# tweeq-Proto_BLE.net
KiCad netlist of a schematic drawn in EAGLE
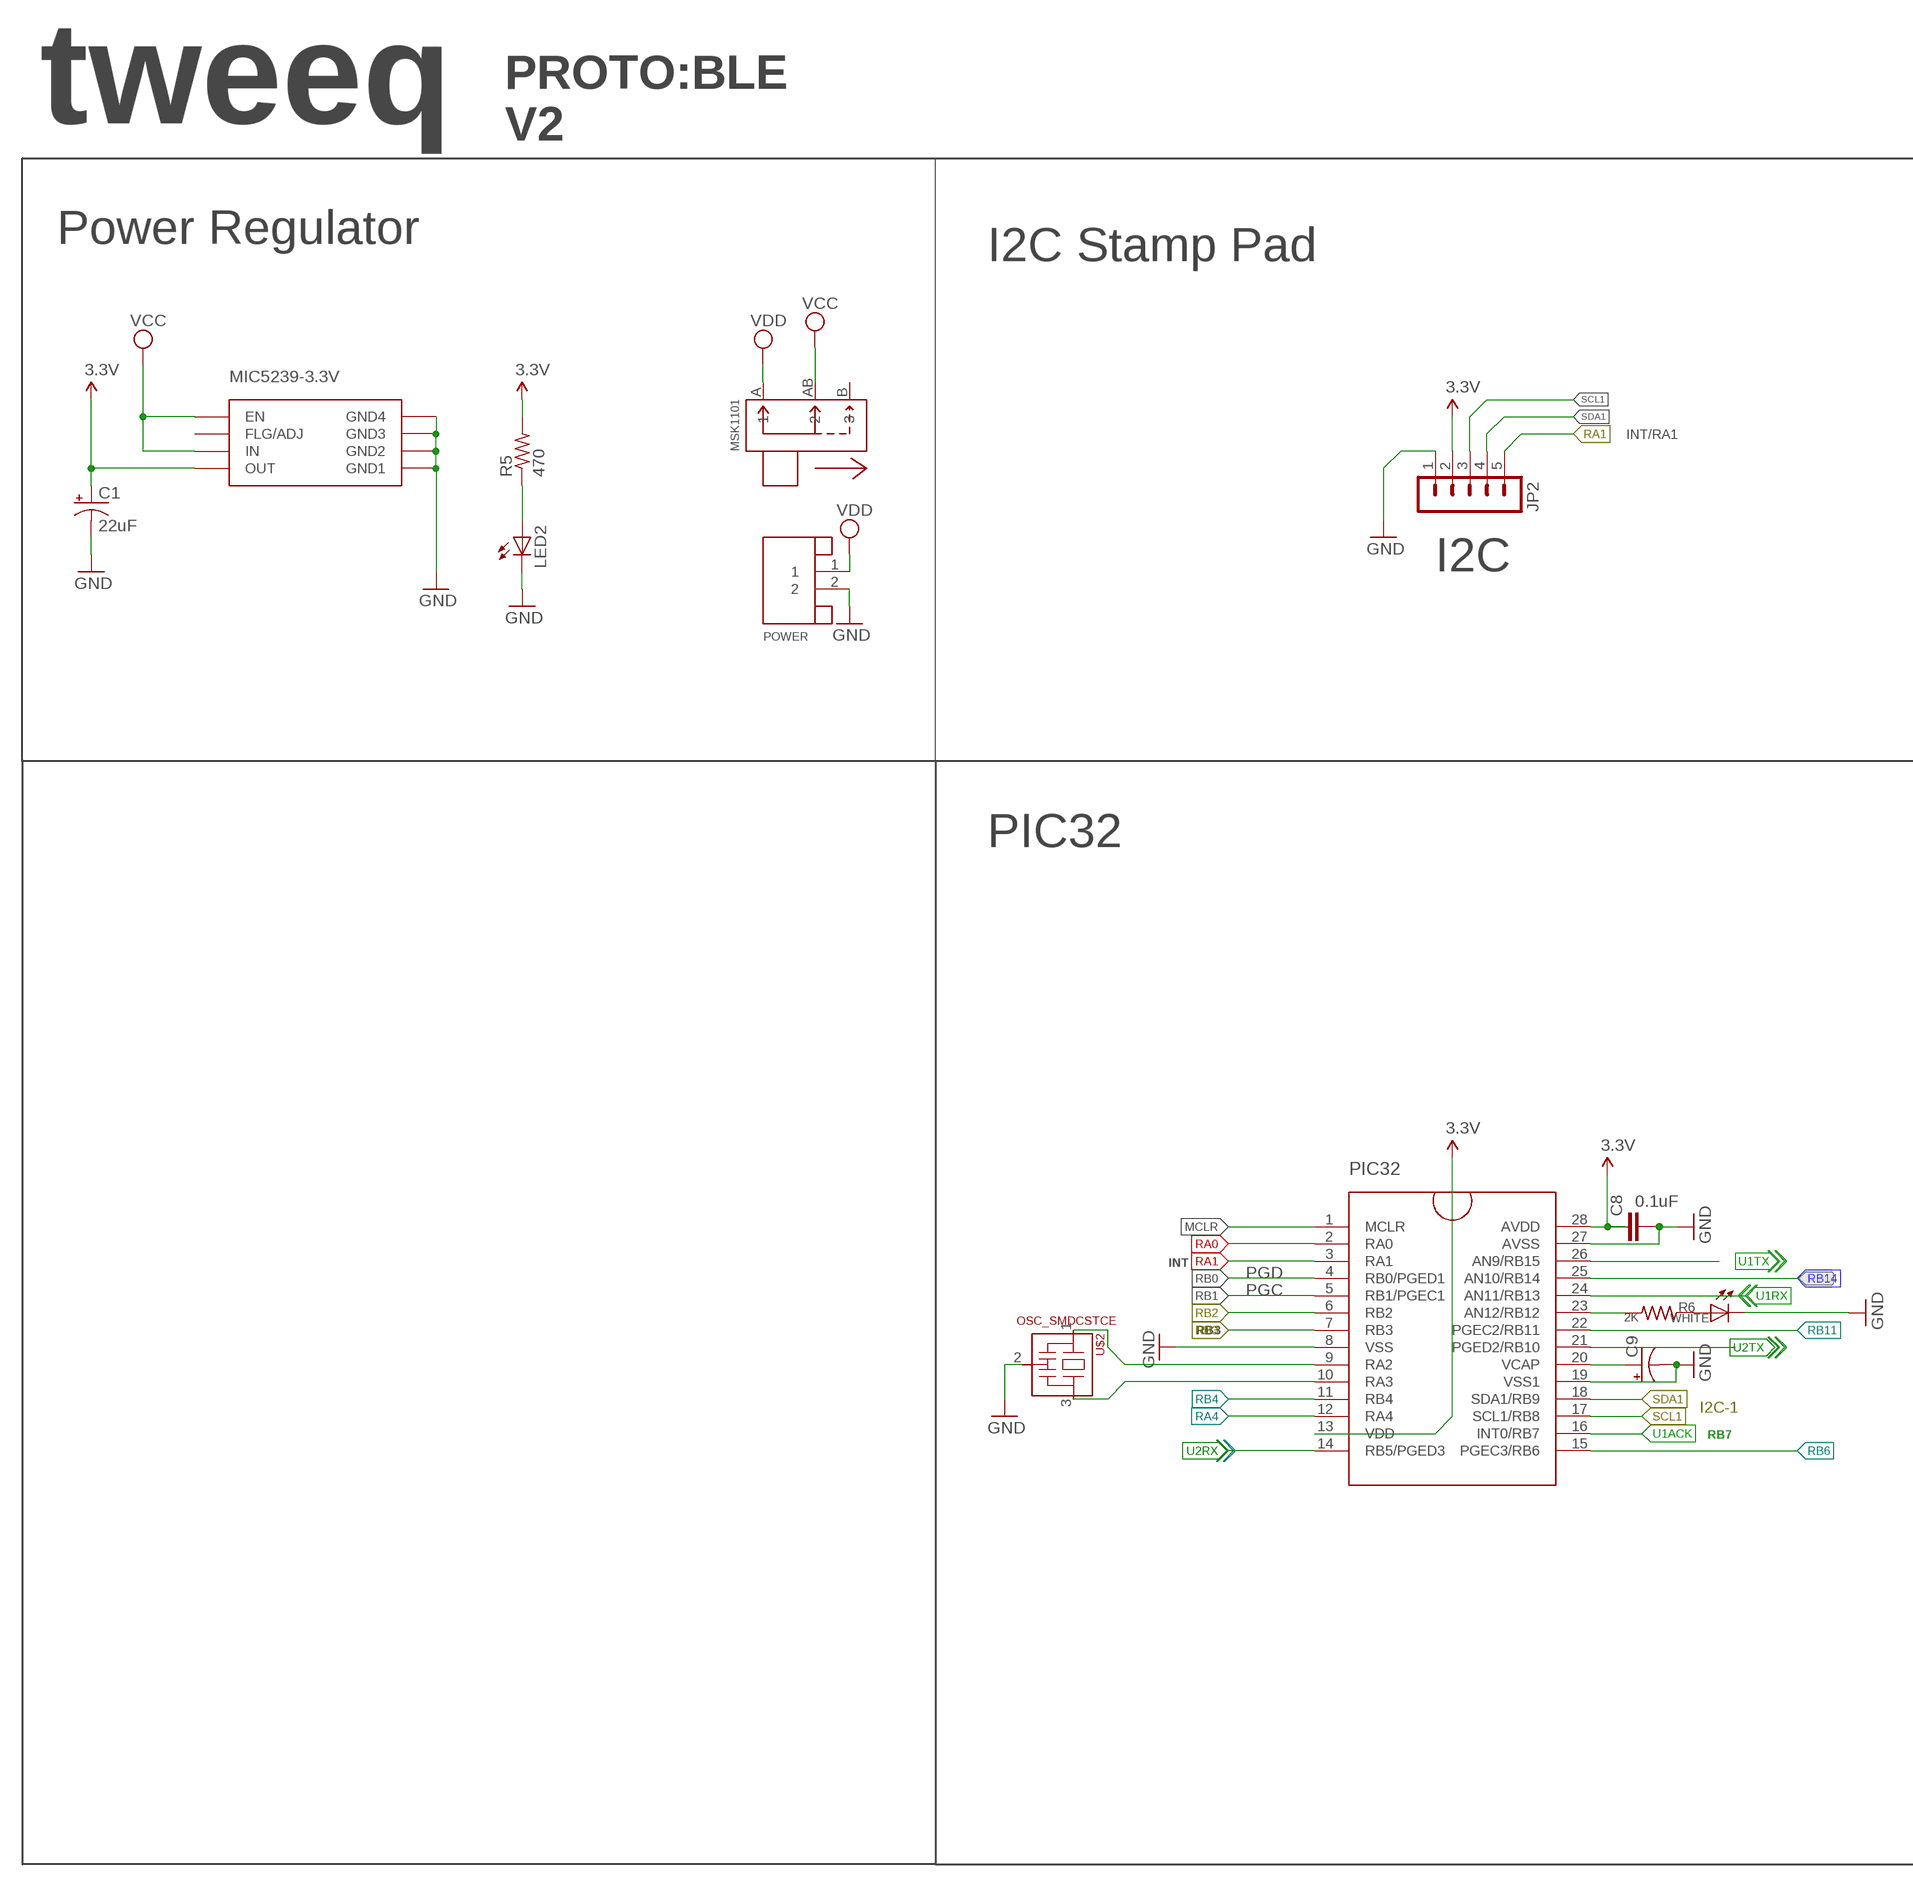
[diagram p0: schematic, sheet 1, part 1 of 2]
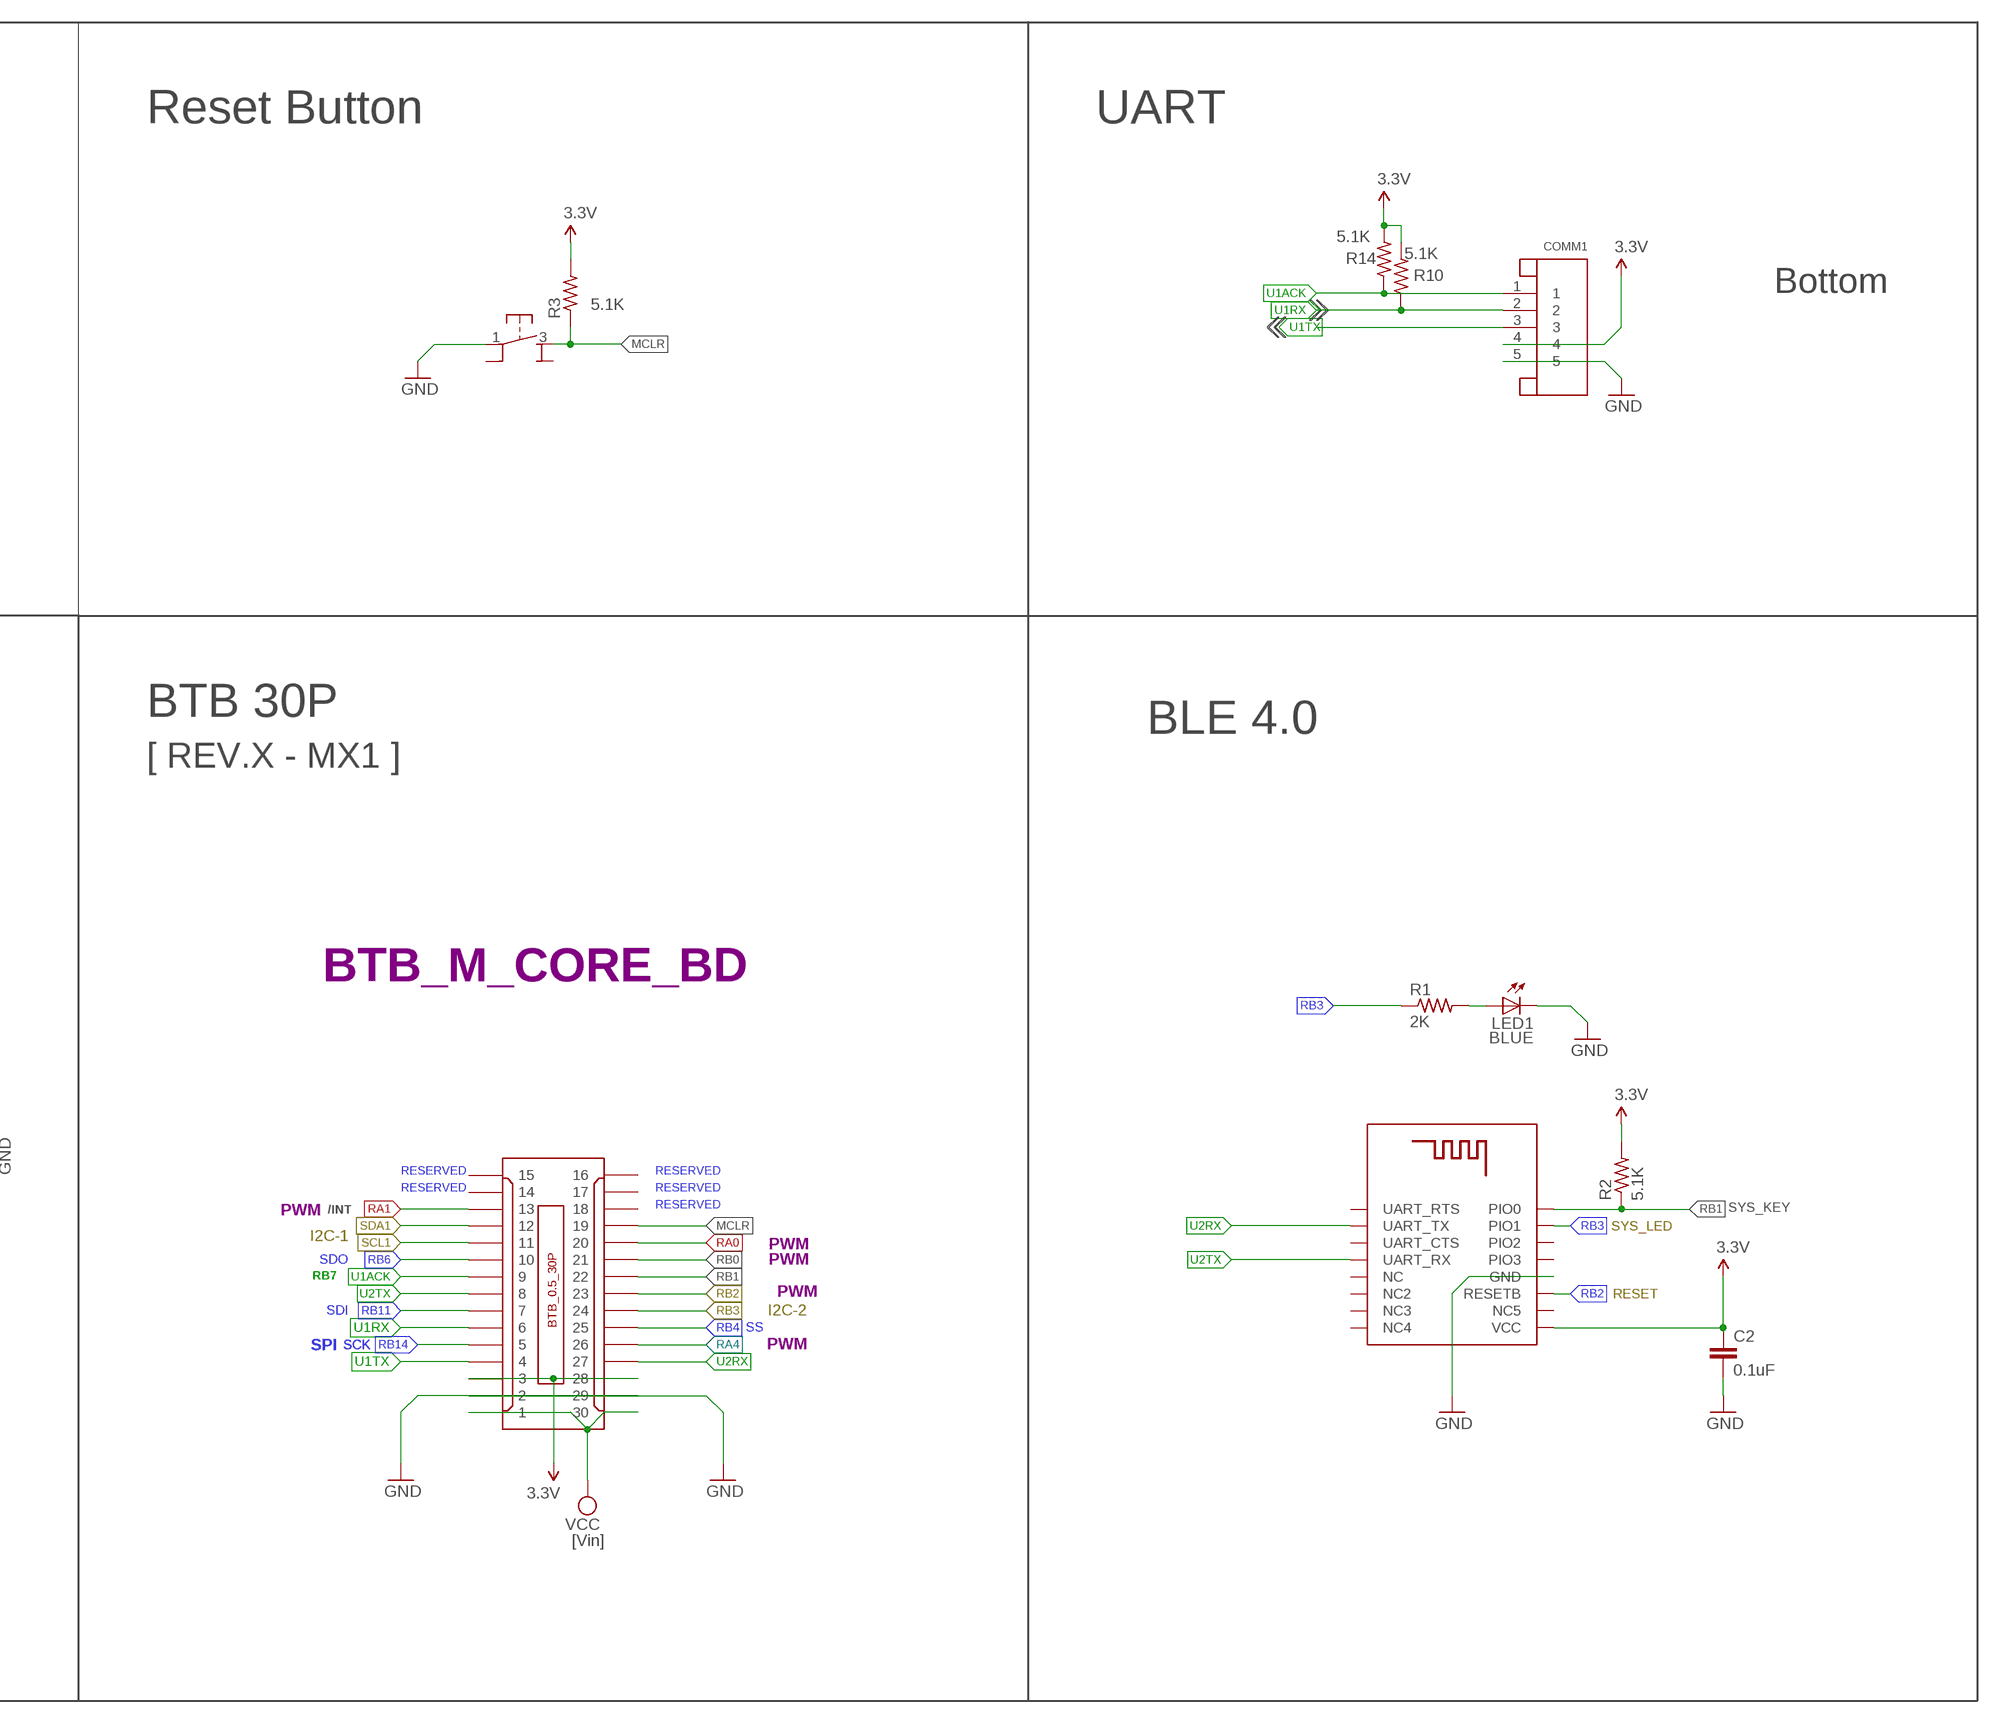
[diagram p1: schematic, sheet 1, part 2 of 2]

(export (version "E")
  (design (tool "Eeschema 10.0.6"))
  (components
    (comp (ref "C1")
      (value "22uF")
      (footprint "eagle-import:SMC_B")
      (libsource (lib "eagle-import") (part "CPOL-USSMCB"))
    )
    (comp (ref "C2")
      (value "0.1uF")
      (footprint "eagle-import:C0402K")
      (libsource (lib "eagle-import") (part "C-EUC0402K"))
    )
    (comp (ref "C8")
      (value "0.1uF")
      (footprint "eagle-import:C0402K")
      (libsource (lib "eagle-import") (part "rcl_C-EUC0402K"))
    )
    (comp (ref "C9")
      (value "CPOL-USA/3216-18R")
      (footprint "eagle-import:A_3216-18R")
      (libsource (lib "eagle-import") (part "CPOL-USA/3216-18R"))
    )
    (comp (ref "COMM1")
      (value "JST-5PINSH")
      (footprint "eagle-import:SH1.0-5PIN")
      (libsource (lib "eagle-import") (part "JST-5PINSH"))
    )
    (comp (ref "JP2")
      (value "M05-11.5MM-SMT")
      (footprint "eagle-import:1X05-1.5MM-SMT")
      (libsource (lib "eagle-import") (part "M05-11.5MM-SMT"))
    )
    (comp (ref "LED1")
      (value "BLUE")
      (footprint "eagle-import:CHIP-LED0805")
      (libsource (lib "eagle-import") (part "LEDCHIP-LED0805"))
    )
    (comp (ref "LED2")
      (value "LEDCHIP-LED0805")
      (footprint "eagle-import:CHIP-LED0805")
      (libsource (lib "eagle-import") (part "LEDCHIP-LED0805"))
    )
    (comp (ref "MIC5239-3.3V")
      (value "MIC5239-MM")
      (footprint "eagle-import:MSOP8")
      (libsource (lib "eagle-import") (part "MIC5239-MM"))
    )
    (comp (ref "MSK1101")
      (value "SLIDE_SWITCH_MINI/MSK1101")
      (footprint "eagle-import:MSK1101")
      (libsource (lib "eagle-import") (part "SLIDE_SWITCH_MINI/MSK1101"))
    )
    (comp (ref "PIC32")
      (value "PIC32MX_1XX_2XX")
      (footprint "eagle-import:SSOP28")
      (libsource (lib "eagle-import") (part "PIC32MX_1XX_2XX"))
    )
    (comp (ref "PIC_LED")
      (value "WHITE")
      (footprint "eagle-import:CHIP-LED0805")
      (libsource (lib "eagle-import") (part "LEDCHIP-LED0805"))
    )
    (comp (ref "POWER")
      (value "JST-2PINSH")
      (footprint "eagle-import:SH1.0-2PIN")
      (libsource (lib "eagle-import") (part "JST-2PINSH"))
    )
    (comp (ref "R1")
      (value "2K")
      (footprint "eagle-import:R0402")
      (libsource (lib "eagle-import") (part "R-US_R0402"))
    )
    (comp (ref "R2")
      (value "5.1K")
      (footprint "eagle-import:R0402")
      (libsource (lib "eagle-import") (part "R-US_R0402"))
    )
    (comp (ref "R3")
      (value "5.1K")
      (footprint "eagle-import:R0402")
      (libsource (lib "eagle-import") (part "R-US_R0402"))
    )
    (comp (ref "R5")
      (value "470")
      (footprint "eagle-import:R0402")
      (libsource (lib "eagle-import") (part "R-US_R0402"))
    )
    (comp (ref "R6")
      (value "2K")
      (footprint "eagle-import:R0402")
      (libsource (lib "eagle-import") (part "R-US_R0402"))
    )
    (comp (ref "R10")
      (value "5.1K")
      (footprint "eagle-import:R0402")
      (libsource (lib "eagle-import") (part "R-US_R0402"))
    )
    (comp (ref "R14")
      (value "5.1K")
      (footprint "eagle-import:R0402")
      (libsource (lib "eagle-import") (part "R-US_R0402"))
    )
    (comp (ref "U$1")
      (value "BTB_CONN_30P/M")
      (footprint "eagle-import:BTB0.5-30M-3.0G")
      (libsource (lib "eagle-import") (part "BTB_CONN_30P/M"))
    )
    (comp (ref "U$2")
      (value "OSC_SMDCSTCE")
      (footprint "eagle-import:CSTCE_RESONATOR_SMD")
      (libsource (lib "eagle-import") (part "OSC_SMDCSTCE"))
    )
    (comp (ref "U$3")
      (value "EBLUE_BLE4.0_HM11HM11")
      (footprint "eagle-import:BLE4.0_HM11")
      (libsource (lib "eagle-import") (part "EBLUE_BLE4.0_HM11HM11"))
    )
    (comp (ref "U$4")
      (value "PB_MICRO_SMT")
      (footprint "eagle-import:PB_SMT_3.5X3X2")
      (libsource (lib "eagle-import") (part "PB_MICRO_SMT"))
    )
  )
  (nets
    (net (code "1") (name "3.3V") (class "Default")
      (node (ref "C1") (pin "+") (pinfunction "+_+") (pintype "passive"))
      (node (ref "C2") (pin "1") (pinfunction "1_1") (pintype "passive"))
      (node (ref "C8") (pin "1") (pinfunction "1_1") (pintype "passive"))
      (node (ref "COMM1") (pin "4") (pinfunction "4_4") (pintype "bidirectional"))
      (node (ref "JP2") (pin "2") (pinfunction "2_2") (pintype "passive"))
      (node (ref "MIC5239-3.3V") (pin "4") (pinfunction "OUT_4") (pintype "bidirectional"))
      (node (ref "PIC32") (pin "13") (pinfunction "VDD_13") (pintype "bidirectional"))
      (node (ref "PIC32") (pin "28") (pinfunction "AVDD_28") (pintype "bidirectional"))
      (node (ref "R10") (pin "2") (pinfunction "2_2") (pintype "passive"))
      (node (ref "R14") (pin "2") (pinfunction "2_2") (pintype "passive"))
      (node (ref "R2") (pin "2") (pinfunction "2_2") (pintype "passive"))
      (node (ref "R3") (pin "2") (pinfunction "2_2") (pintype "passive"))
      (node (ref "R5") (pin "2") (pinfunction "2_2") (pintype "passive"))
      (node (ref "U$1") (pin "28") (pinfunction "28_28") (pintype "bidirectional"))
      (node (ref "U$1") (pin "3") (pinfunction "3_3") (pintype "bidirectional"))
      (node (ref "U$3") (pin "P$9") (pinfunction "VCC_P$9") (pintype "power_in"))
    )
    (net (code "2") (name "GND") (class "Default")
      (node (ref "C1") (pin "-") (pinfunction "-_-") (pintype "passive"))
      (node (ref "C2") (pin "2") (pinfunction "2_2") (pintype "passive"))
      (node (ref "C8") (pin "2") (pinfunction "2_2") (pintype "passive"))
      (node (ref "C9") (pin "-") (pinfunction "-_-") (pintype "passive"))
      (node (ref "COMM1") (pin "5") (pinfunction "5_5") (pintype "bidirectional"))
      (node (ref "JP2") (pin "1") (pinfunction "1_1") (pintype "passive"))
      (node (ref "LED1") (pin "C") (pinfunction "C_C") (pintype "passive"))
      (node (ref "LED2") (pin "C") (pinfunction "C_C") (pintype "passive"))
      (node (ref "MIC5239-3.3V") (pin "5") (pinfunction "GND1_5") (pintype "bidirectional"))
      (node (ref "MIC5239-3.3V") (pin "6") (pinfunction "GND2_6") (pintype "bidirectional"))
      (node (ref "MIC5239-3.3V") (pin "7") (pinfunction "GND3_7") (pintype "bidirectional"))
      (node (ref "MIC5239-3.3V") (pin "8") (pinfunction "GND4_8") (pintype "bidirectional"))
      (node (ref "PIC32") (pin "19") (pinfunction "VSS1_19") (pintype "bidirectional"))
      (node (ref "PIC32") (pin "27") (pinfunction "AVSS_27") (pintype "bidirectional"))
      (node (ref "PIC32") (pin "8") (pinfunction "VSS_8") (pintype "bidirectional"))
      (node (ref "PIC_LED") (pin "C") (pinfunction "C_C") (pintype "passive"))
      (node (ref "POWER") (pin "2") (pinfunction "2_2") (pintype "bidirectional"))
      (node (ref "U$1") (pin "2") (pinfunction "2_2") (pintype "bidirectional"))
      (node (ref "U$1") (pin "29") (pinfunction "29_29") (pintype "bidirectional"))
      (node (ref "U$2") (pin "2") (pinfunction "VSS_2") (pintype "power_in"))
      (node (ref "U$3") (pin "P$12") (pinfunction "GND_P$12") (pintype "power_in"))
      (node (ref "U$4") (pin "1") (pinfunction "1_1") (pintype "passive"))
    )
    (net (code "3") (name "MCLR") (class "Default")
      (node (ref "PIC32") (pin "1") (pinfunction "MCLR_1") (pintype "bidirectional"))
      (node (ref "R3") (pin "1") (pinfunction "1_1") (pintype "passive"))
      (node (ref "U$1") (pin "19") (pinfunction "19_19") (pintype "bidirectional"))
      (node (ref "U$4") (pin "3") (pinfunction "2_3") (pintype "passive"))
    )
    (net (code "4") (name "Net-(LED1-PadA)") (class "Default")
      (node (ref "LED1") (pin "A") (pinfunction "A_A") (pintype "passive"))
      (node (ref "R1") (pin "2") (pinfunction "2_2") (pintype "passive"))
    )
    (net (code "5") (name "Net-(LED2-PadA)") (class "Default")
      (node (ref "LED2") (pin "A") (pinfunction "A_A") (pintype "passive"))
      (node (ref "R5") (pin "1") (pinfunction "1_1") (pintype "passive"))
    )
    (net (code "6") (name "Net-(PIC32-AN12{slash}RB12)") (class "Default")
      (node (ref "PIC32") (pin "23") (pinfunction "AN12/RB12_23") (pintype "bidirectional"))
      (node (ref "R6") (pin "2") (pinfunction "2_2") (pintype "passive"))
    )
    (net (code "7") (name "Net-(PIC32-RA2)") (class "Default")
      (node (ref "PIC32") (pin "9") (pinfunction "RA2_9") (pintype "bidirectional"))
      (node (ref "U$2") (pin "1") (pinfunction "1_1") (pintype "output"))
    )
    (net (code "8") (name "Net-(PIC32-RA3)") (class "Default")
      (node (ref "PIC32") (pin "10") (pinfunction "RA3_10") (pintype "bidirectional"))
      (node (ref "U$2") (pin "3") (pinfunction "3_3") (pintype "input"))
    )
    (net (code "9") (name "Net-(PIC32-VCAP)") (class "Default")
      (node (ref "C9") (pin "+") (pinfunction "+_+") (pintype "passive"))
      (node (ref "PIC32") (pin "20") (pinfunction "VCAP_20") (pintype "bidirectional"))
    )
    (net (code "10") (name "Net-(PIC_LED-PadA)") (class "Default")
      (node (ref "PIC_LED") (pin "A") (pinfunction "A_A") (pintype "passive"))
      (node (ref "R6") (pin "1") (pinfunction "1_1") (pintype "passive"))
    )
    (net (code "11") (name "RA0") (class "Default")
      (node (ref "PIC32") (pin "2") (pinfunction "RA0_2") (pintype "bidirectional"))
      (node (ref "U$1") (pin "20") (pinfunction "20_20") (pintype "bidirectional"))
    )
    (net (code "12") (name "RA1") (class "Default")
      (node (ref "JP2") (pin "5") (pinfunction "5_5") (pintype "passive"))
      (node (ref "PIC32") (pin "3") (pinfunction "RA1_3") (pintype "bidirectional"))
      (node (ref "U$1") (pin "13") (pinfunction "13_13") (pintype "bidirectional"))
    )
    (net (code "13") (name "RA4") (class "Default")
      (node (ref "PIC32") (pin "12") (pinfunction "RA4_12") (pintype "bidirectional"))
      (node (ref "U$1") (pin "26") (pinfunction "26_26") (pintype "bidirectional"))
    )
    (net (code "14") (name "RB0") (class "Default")
      (node (ref "PIC32") (pin "4") (pinfunction "RB0/PGED1_4") (pintype "bidirectional"))
      (node (ref "U$1") (pin "21") (pinfunction "21_21") (pintype "bidirectional"))
    )
    (net (code "15") (name "RB1") (class "Default")
      (node (ref "PIC32") (pin "5") (pinfunction "RB1/PGEC1_5") (pintype "bidirectional"))
      (node (ref "R2") (pin "1") (pinfunction "1_1") (pintype "passive"))
      (node (ref "U$1") (pin "22") (pinfunction "22_22") (pintype "bidirectional"))
      (node (ref "U$3") (pin "P$16") (pinfunction "PIO0_P$16") (pintype "bidirectional"))
    )
    (net (code "16") (name "RB2") (class "Default")
      (node (ref "PIC32") (pin "6") (pinfunction "RB2_6") (pintype "bidirectional"))
      (node (ref "U$1") (pin "23") (pinfunction "23_23") (pintype "bidirectional"))
      (node (ref "U$3") (pin "P$11") (pinfunction "RESETB_P$11") (pintype "bidirectional"))
    )
    (net (code "17") (name "RB3") (class "Default")
      (node (ref "PIC32") (pin "7") (pinfunction "RB3_7") (pintype "bidirectional"))
      (node (ref "R1") (pin "1") (pinfunction "1_1") (pintype "passive"))
      (node (ref "U$1") (pin "24") (pinfunction "24_24") (pintype "bidirectional"))
      (node (ref "U$3") (pin "P$15") (pinfunction "PIO1_P$15") (pintype "bidirectional"))
    )
    (net (code "18") (name "RB4") (class "Default")
      (node (ref "PIC32") (pin "11") (pinfunction "RB4_11") (pintype "bidirectional"))
      (node (ref "U$1") (pin "25") (pinfunction "25_25") (pintype "bidirectional"))
    )
    (net (code "19") (name "RB6") (class "Default")
      (node (ref "PIC32") (pin "15") (pinfunction "PGEC3/RB6_15") (pintype "bidirectional"))
      (node (ref "U$1") (pin "10") (pinfunction "10_10") (pintype "bidirectional"))
    )
    (net (code "20") (name "RB11") (class "Default")
      (node (ref "PIC32") (pin "22") (pinfunction "PGEC2/RB11_22") (pintype "bidirectional"))
      (node (ref "U$1") (pin "7") (pinfunction "7_7") (pintype "bidirectional"))
    )
    (net (code "21") (name "RB14") (class "Default")
      (node (ref "PIC32") (pin "25") (pinfunction "AN10/RB14_25") (pintype "bidirectional"))
      (node (ref "U$1") (pin "5") (pinfunction "5_5") (pintype "bidirectional"))
    )
    (net (code "22") (name "SCL1") (class "Default")
      (node (ref "JP2") (pin "3") (pinfunction "3_3") (pintype "passive"))
      (node (ref "PIC32") (pin "17") (pinfunction "SCL1/RB8_17") (pintype "bidirectional"))
      (node (ref "U$1") (pin "11") (pinfunction "11_11") (pintype "bidirectional"))
    )
    (net (code "23") (name "SDA1") (class "Default")
      (node (ref "JP2") (pin "4") (pinfunction "4_4") (pintype "passive"))
      (node (ref "PIC32") (pin "18") (pinfunction "SDA1/RB9_18") (pintype "bidirectional"))
      (node (ref "U$1") (pin "12") (pinfunction "12_12") (pintype "bidirectional"))
    )
    (net (code "24") (name "U1ACK") (class "Default")
      (node (ref "COMM1") (pin "1") (pinfunction "1_1") (pintype "bidirectional"))
      (node (ref "PIC32") (pin "16") (pinfunction "INT0/RB7_16") (pintype "bidirectional"))
      (node (ref "R14") (pin "1") (pinfunction "1_1") (pintype "passive"))
      (node (ref "U$1") (pin "9") (pinfunction "9_9") (pintype "bidirectional"))
    )
    (net (code "25") (name "U1RX") (class "Default")
      (node (ref "COMM1") (pin "2") (pinfunction "2_2") (pintype "bidirectional"))
      (node (ref "PIC32") (pin "24") (pinfunction "AN11/RB13_24") (pintype "bidirectional"))
      (node (ref "R10") (pin "1") (pinfunction "1_1") (pintype "passive"))
      (node (ref "U$1") (pin "6") (pinfunction "6_6") (pintype "bidirectional"))
    )
    (net (code "26") (name "U1TX") (class "Default")
      (node (ref "COMM1") (pin "3") (pinfunction "3_3") (pintype "bidirectional"))
      (node (ref "PIC32") (pin "26") (pinfunction "AN9/RB15_26") (pintype "bidirectional"))
      (node (ref "U$1") (pin "4") (pinfunction "4_4") (pintype "bidirectional"))
    )
    (net (code "27") (name "U2RX") (class "Default")
      (node (ref "PIC32") (pin "14") (pinfunction "RB5/PGED3_14") (pintype "bidirectional"))
      (node (ref "U$1") (pin "27") (pinfunction "27_27") (pintype "bidirectional"))
      (node (ref "U$3") (pin "P$2") (pinfunction "UART_TX_P$2") (pintype "bidirectional"))
    )
    (net (code "28") (name "U2TX") (class "Default")
      (node (ref "PIC32") (pin "21") (pinfunction "PGED2/RB10_21") (pintype "bidirectional"))
      (node (ref "U$1") (pin "8") (pinfunction "8_8") (pintype "bidirectional"))
      (node (ref "U$3") (pin "P$4") (pinfunction "UART_RX_P$4") (pintype "bidirectional"))
    )
    (net (code "29") (name "VCC") (class "Default")
      (node (ref "MIC5239-3.3V") (pin "1") (pinfunction "EN_1") (pintype "bidirectional"))
      (node (ref "MIC5239-3.3V") (pin "3") (pinfunction "IN_3") (pintype "bidirectional"))
      (node (ref "MSK1101") (pin "AB") (pinfunction "2_AB") (pintype "bidirectional"))
      (node (ref "U$1") (pin "1") (pinfunction "1_1") (pintype "bidirectional"))
      (node (ref "U$1") (pin "30") (pinfunction "30_30") (pintype "bidirectional"))
    )
    (net (code "30") (name "VDD") (class "Default")
      (node (ref "MSK1101") (pin "A") (pinfunction "1_A") (pintype "bidirectional"))
      (node (ref "POWER") (pin "1") (pinfunction "1_1") (pintype "bidirectional"))
    )
    (net (code "31") (name "unconnected-(MIC5239-3.3V-FLG{slash}ADJ-Pad2)") (class "Default")
      (node (ref "MIC5239-3.3V") (pin "2") (pinfunction "FLG/ADJ_2") (pintype "bidirectional"))
    )
    (net (code "32") (name "unconnected-(MSK1101-3-PadB)") (class "Default")
      (node (ref "MSK1101") (pin "B") (pinfunction "3_B") (pintype "bidirectional"))
    )
    (net (code "33") (name "unconnected-(U$1-Pad14)") (class "Default")
      (node (ref "U$1") (pin "14") (pinfunction "14_14") (pintype "bidirectional"))
    )
    (net (code "34") (name "unconnected-(U$1-Pad15)") (class "Default")
      (node (ref "U$1") (pin "15") (pinfunction "15_15") (pintype "bidirectional"))
    )
    (net (code "35") (name "unconnected-(U$1-Pad16)") (class "Default")
      (node (ref "U$1") (pin "16") (pinfunction "16_16") (pintype "bidirectional"))
    )
    (net (code "36") (name "unconnected-(U$1-Pad17)") (class "Default")
      (node (ref "U$1") (pin "17") (pinfunction "17_17") (pintype "bidirectional"))
    )
    (net (code "37") (name "unconnected-(U$1-Pad18)") (class "Default")
      (node (ref "U$1") (pin "18") (pinfunction "18_18") (pintype "bidirectional"))
    )
    (net (code "38") (name "unconnected-(U$3-NC-PadP$5)") (class "Default")
      (node (ref "U$3") (pin "P$5") (pinfunction "NC_P$5") (pintype "no_connect"))
    )
    (net (code "39") (name "unconnected-(U$3-NC2-PadP$6)") (class "Default")
      (node (ref "U$3") (pin "P$6") (pinfunction "NC2_P$6") (pintype "no_connect"))
    )
    (net (code "40") (name "unconnected-(U$3-NC3-PadP$7)") (class "Default")
      (node (ref "U$3") (pin "P$7") (pinfunction "NC3_P$7") (pintype "no_connect"))
    )
    (net (code "41") (name "unconnected-(U$3-NC4-PadP$8)") (class "Default")
      (node (ref "U$3") (pin "P$8") (pinfunction "NC4_P$8") (pintype "no_connect"))
    )
    (net (code "42") (name "unconnected-(U$3-NC5-PadP$10)") (class "Default")
      (node (ref "U$3") (pin "P$10") (pinfunction "NC5_P$10") (pintype "no_connect"))
    )
    (net (code "43") (name "unconnected-(U$3-PIO2-PadP$14)") (class "Default")
      (node (ref "U$3") (pin "P$14") (pinfunction "PIO2_P$14") (pintype "bidirectional"))
    )
    (net (code "44") (name "unconnected-(U$3-PIO3-PadP$13)") (class "Default")
      (node (ref "U$3") (pin "P$13") (pinfunction "PIO3_P$13") (pintype "bidirectional"))
    )
    (net (code "45") (name "unconnected-(U$3-UART_CTS-PadP$3)") (class "Default")
      (node (ref "U$3") (pin "P$3") (pinfunction "UART_CTS_P$3") (pintype "bidirectional"))
    )
    (net (code "46") (name "unconnected-(U$3-UART_RTS-PadP$1)") (class "Default")
      (node (ref "U$3") (pin "P$1") (pinfunction "UART_RTS_P$1") (pintype "bidirectional"))
    )
    (net (code "47") (name "unconnected-(U$4-1A-Pad2)") (class "Default")
      (node (ref "U$4") (pin "2") (pinfunction "1A_2") (pintype "passive"))
    )
    (net (code "48") (name "unconnected-(U$4-2A-Pad4)") (class "Default")
      (node (ref "U$4") (pin "4") (pinfunction "2A_4") (pintype "passive"))
    )
  )
)
